# Projet_Schematics.net
KiCad netlist of a schematic drawn in EAGLE
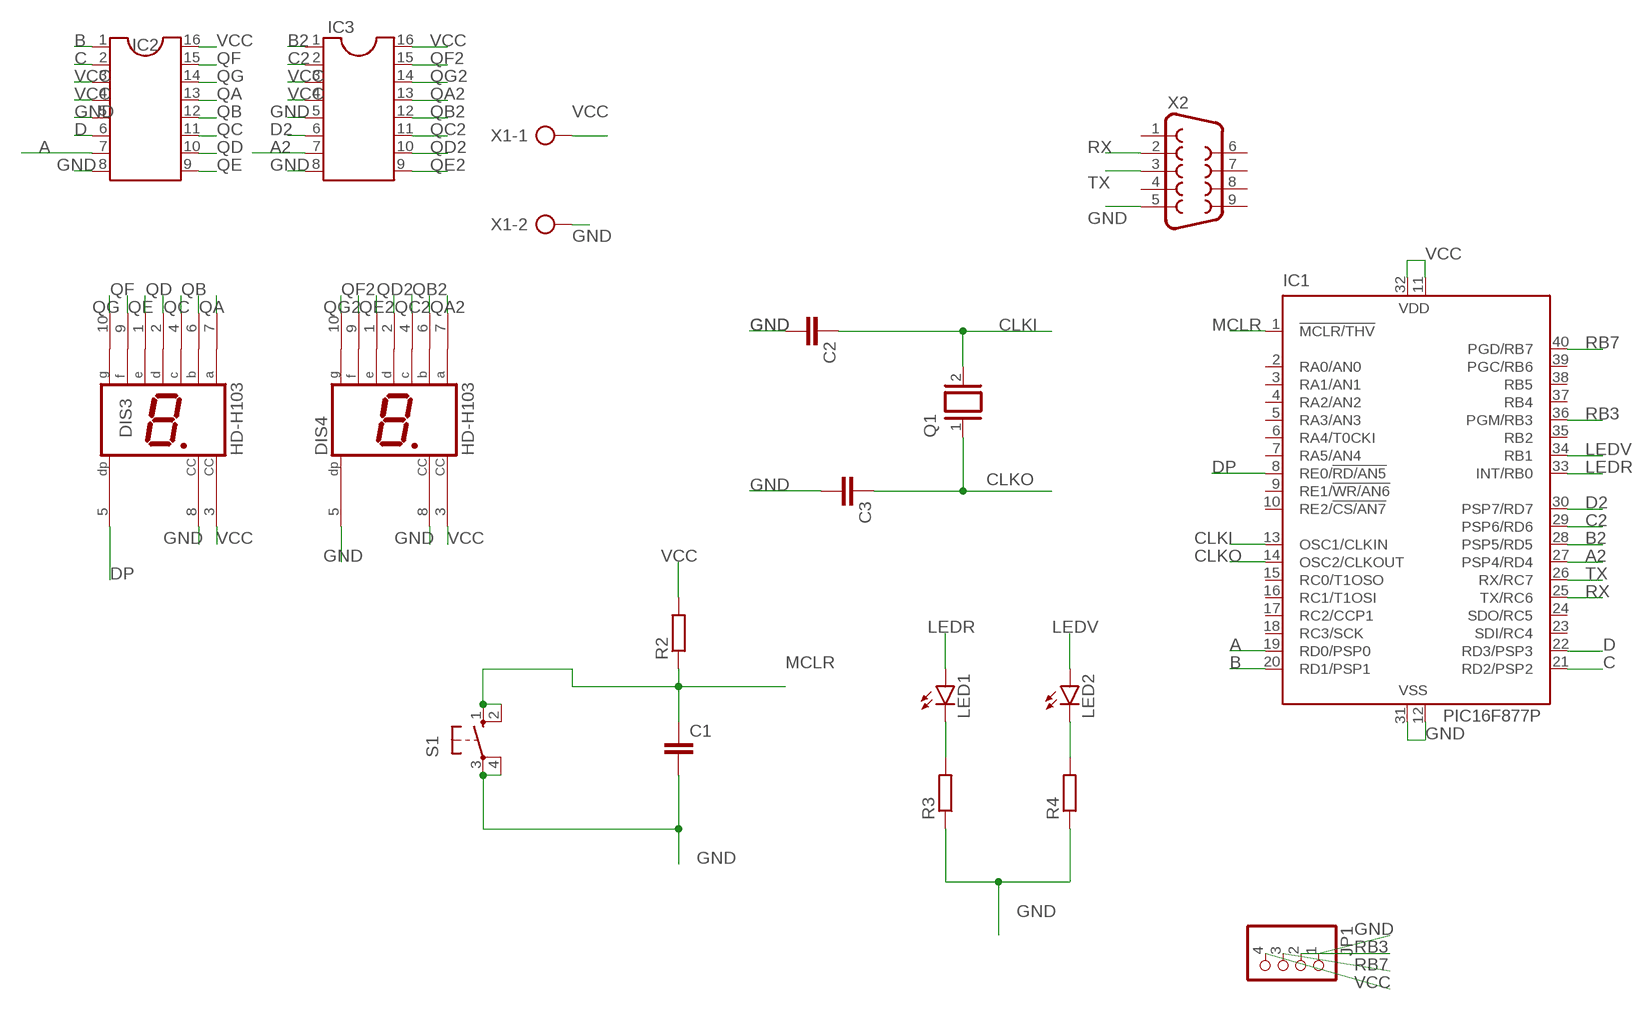
[diagram p0: schematic, sheet 1]

(export (version "E")
  (design (tool "Eeschema 10.0.6"))
  (components
    (comp (ref "C1")
      (value "C-EU025-030X050")
      (footprint "eagle-import:C025-030X050")
      (libsource (lib "eagle-import") (part "C-EU025-030X050"))
    )
    (comp (ref "C2")
      (value "C-EU025-030X050")
      (footprint "eagle-import:C025-030X050")
      (libsource (lib "eagle-import") (part "C-EU025-030X050"))
    )
    (comp (ref "C3")
      (value "C-EU025-030X050")
      (footprint "eagle-import:C025-030X050")
      (libsource (lib "eagle-import") (part "C-EU025-030X050"))
    )
    (comp (ref "DIS3")
      (value "HD-H103")
      (footprint "eagle-import:HDSP-M")
      (libsource (lib "eagle-import") (part "HD-H103"))
    )
    (comp (ref "DIS4")
      (value "HD-H103")
      (footprint "eagle-import:HDSP-M")
      (libsource (lib "eagle-import") (part "HD-H103"))
    )
    (comp (ref "IC1")
      (value "PIC16F877P")
      (footprint "eagle-import:DIL40")
      (fields (field (name "MF") "MICROCHIP") (field (name "MPN") "PIC16F877-04/P"))
      (libsource (lib "eagle-import") (part "PIC16F87P7"))
    )
    (comp (ref "IC2")
      (value "DIL16")
      (footprint "eagle-import:DIL16")
      (libsource (lib "eagle-import") (part "DIL16"))
    )
    (comp (ref "IC3")
      (value "DIL16")
      (footprint "eagle-import:DIL16")
      (libsource (lib "eagle-import") (part "DIL16"))
    )
    (comp (ref "JP1")
      (value "PINHD-1X4")
      (footprint "eagle-import:1X04")
      (libsource (lib "eagle-import") (part "PINHD-1X4"))
    )
    (comp (ref "LED1")
      (value "LED5MM")
      (footprint "eagle-import:LED5MM")
      (libsource (lib "eagle-import") (part "LED5MM"))
    )
    (comp (ref "LED2")
      (value "LED5MM")
      (footprint "eagle-import:LED5MM")
      (libsource (lib "eagle-import") (part "LED5MM"))
    )
    (comp (ref "Q1")
      (value "XTAL/S")
      (footprint "eagle-import:QS")
      (libsource (lib "eagle-import") (part "XTAL/S"))
    )
    (comp (ref "R2")
      (value "R-EU_0204/7")
      (footprint "eagle-import:0204_7")
      (libsource (lib "eagle-import") (part "R-EU_0204/7"))
    )
    (comp (ref "R3")
      (value "R-EU_0204/7")
      (footprint "eagle-import:0204_7")
      (libsource (lib "eagle-import") (part "R-EU_0204/7"))
    )
    (comp (ref "R4")
      (value "R-EU_0204/7")
      (footprint "eagle-import:0204_7")
      (libsource (lib "eagle-import") (part "R-EU_0204/7"))
    )
    (comp (ref "S1")
      (value "10-XX")
      (footprint "eagle-import:B3F-10XX")
      (fields (field (name "MPN") "B3F-1000"))
      (libsource (lib "eagle-import") (part "10-XX"))
    )
    (comp (ref "X1")
      (value "AK300/2")
      (footprint "eagle-import:AK300_2")
      (libsource (lib "eagle-import") (part "AK300/2"))
    )
    (comp (ref "X2")
      (value "F09H")
      (footprint "eagle-import:F09H")
      (libsource (lib "eagle-import") (part "F09H"))
    )
  )
  (nets
    (net (code "1") (name "/A") (class "Default")
      (node (ref "IC1") (pin "19") (pinfunction "RD0/PSP0_19") (pintype "bidirectional"))
      (node (ref "IC2") (pin "7") (pinfunction "7_7") (pintype "passive"))
    )
    (net (code "2") (name "/A2") (class "Default")
      (node (ref "IC1") (pin "27") (pinfunction "PSP4/RD4_27") (pintype "bidirectional"))
      (node (ref "IC3") (pin "7") (pinfunction "7_7") (pintype "passive"))
    )
    (net (code "3") (name "/B") (class "Default")
      (node (ref "IC1") (pin "20") (pinfunction "RD1/PSP1_20") (pintype "bidirectional"))
      (node (ref "IC2") (pin "1") (pinfunction "1_1") (pintype "passive"))
    )
    (net (code "4") (name "/B2") (class "Default")
      (node (ref "IC1") (pin "28") (pinfunction "PSP5/RD5_28") (pintype "bidirectional"))
      (node (ref "IC3") (pin "1") (pinfunction "1_1") (pintype "passive"))
    )
    (net (code "5") (name "/C") (class "Default")
      (node (ref "IC1") (pin "21") (pinfunction "RD2/PSP2_21") (pintype "bidirectional"))
      (node (ref "IC2") (pin "2") (pinfunction "2_2") (pintype "passive"))
    )
    (net (code "6") (name "/C2") (class "Default")
      (node (ref "IC1") (pin "29") (pinfunction "PSP6/RD6_29") (pintype "bidirectional"))
      (node (ref "IC3") (pin "2") (pinfunction "2_2") (pintype "passive"))
    )
    (net (code "7") (name "/CLKI") (class "Default")
      (node (ref "C2") (pin "1") (pinfunction "1_1") (pintype "passive"))
      (node (ref "IC1") (pin "13") (pinfunction "OSC1/CLKIN_13") (pintype "input"))
      (node (ref "Q1") (pin "2") (pinfunction "2_2") (pintype "passive"))
    )
    (net (code "8") (name "/CLKO") (class "Default")
      (node (ref "C3") (pin "1") (pinfunction "1_1") (pintype "passive"))
      (node (ref "IC1") (pin "14") (pinfunction "OSC2/CLKOUT_14") (pintype "output"))
      (node (ref "Q1") (pin "1") (pinfunction "1_1") (pintype "passive"))
    )
    (net (code "9") (name "/D") (class "Default")
      (node (ref "IC1") (pin "22") (pinfunction "RD3/PSP3_22") (pintype "bidirectional"))
      (node (ref "IC2") (pin "6") (pinfunction "6_6") (pintype "passive"))
    )
    (net (code "10") (name "/D2") (class "Default")
      (node (ref "IC1") (pin "30") (pinfunction "PSP7/RD7_30") (pintype "bidirectional"))
      (node (ref "IC3") (pin "6") (pinfunction "6_6") (pintype "passive"))
    )
    (net (code "11") (name "/DP") (class "Default")
      (node (ref "DIS3") (pin "5") (pinfunction "DP_5") (pintype "passive"))
      (node (ref "IC1") (pin "8") (pinfunction "RE0/~{RD/AN5}_8") (pintype "bidirectional"))
    )
    (net (code "12") (name "/GND") (class "Default")
      (node (ref "C1") (pin "2") (pinfunction "2_2") (pintype "passive"))
      (node (ref "C2") (pin "2") (pinfunction "2_2") (pintype "passive"))
      (node (ref "C3") (pin "2") (pinfunction "2_2") (pintype "passive"))
      (node (ref "DIS3") (pin "8") (pinfunction "CC_8") (pintype "passive"))
      (node (ref "DIS4") (pin "5") (pinfunction "DP_5") (pintype "passive"))
      (node (ref "DIS4") (pin "8") (pinfunction "CC_8") (pintype "passive"))
      (node (ref "IC1") (pin "12") (pinfunction "VSS_12") (pintype "power_in"))
      (node (ref "IC1") (pin "31") (pinfunction "VSS_31") (pintype "power_in"))
      (node (ref "IC2") (pin "5") (pinfunction "5_5") (pintype "passive"))
      (node (ref "IC2") (pin "8") (pinfunction "8_8") (pintype "passive"))
      (node (ref "IC3") (pin "5") (pinfunction "5_5") (pintype "passive"))
      (node (ref "IC3") (pin "8") (pinfunction "8_8") (pintype "passive"))
      (node (ref "JP1") (pin "1") (pinfunction "1_1") (pintype "passive"))
      (node (ref "R3") (pin "1") (pinfunction "1_1") (pintype "passive"))
      (node (ref "R4") (pin "1") (pinfunction "1_1") (pintype "passive"))
      (node (ref "S1") (pin "3") (pinfunction "P_3") (pintype "passive"))
      (node (ref "S1") (pin "4") (pinfunction "P1_4") (pintype "passive"))
      (node (ref "X1") (pin "2") (pinfunction "KL_2") (pintype "passive"))
      (node (ref "X2") (pin "5") (pinfunction "5_5") (pintype "passive"))
    )
    (net (code "13") (name "/LEDR") (class "Default")
      (node (ref "IC1") (pin "33") (pinfunction "INT/RB0_33") (pintype "bidirectional"))
      (node (ref "LED1") (pin "A") (pinfunction "A_A") (pintype "passive"))
    )
    (net (code "14") (name "/LEDV") (class "Default")
      (node (ref "IC1") (pin "34") (pinfunction "RB1_34") (pintype "bidirectional"))
      (node (ref "LED2") (pin "A") (pinfunction "A_A") (pintype "passive"))
    )
    (net (code "15") (name "/MCLR") (class "Default")
      (node (ref "C1") (pin "1") (pinfunction "1_1") (pintype "passive"))
      (node (ref "IC1") (pin "1") (pinfunction "~{MCLR/THV}_1") (pintype "input"))
      (node (ref "R2") (pin "1") (pinfunction "1_1") (pintype "passive"))
      (node (ref "S1") (pin "1") (pinfunction "S_1") (pintype "passive"))
      (node (ref "S1") (pin "2") (pinfunction "S1_2") (pintype "passive"))
    )
    (net (code "16") (name "/QA") (class "Default")
      (node (ref "DIS3") (pin "7") (pinfunction "A_7") (pintype "passive"))
      (node (ref "IC2") (pin "13") (pinfunction "13_13") (pintype "passive"))
    )
    (net (code "17") (name "/QA2") (class "Default")
      (node (ref "DIS4") (pin "7") (pinfunction "A_7") (pintype "passive"))
      (node (ref "IC3") (pin "13") (pinfunction "13_13") (pintype "passive"))
    )
    (net (code "18") (name "/QB") (class "Default")
      (node (ref "DIS3") (pin "6") (pinfunction "B_6") (pintype "passive"))
      (node (ref "IC2") (pin "12") (pinfunction "12_12") (pintype "passive"))
    )
    (net (code "19") (name "/QB2") (class "Default")
      (node (ref "DIS4") (pin "6") (pinfunction "B_6") (pintype "passive"))
      (node (ref "IC3") (pin "12") (pinfunction "12_12") (pintype "passive"))
    )
    (net (code "20") (name "/QC") (class "Default")
      (node (ref "DIS3") (pin "4") (pinfunction "C_4") (pintype "passive"))
      (node (ref "IC2") (pin "11") (pinfunction "11_11") (pintype "passive"))
    )
    (net (code "21") (name "/QC2") (class "Default")
      (node (ref "DIS4") (pin "4") (pinfunction "C_4") (pintype "passive"))
      (node (ref "IC3") (pin "11") (pinfunction "11_11") (pintype "passive"))
    )
    (net (code "22") (name "/QD") (class "Default")
      (node (ref "DIS3") (pin "2") (pinfunction "D_2") (pintype "passive"))
      (node (ref "IC2") (pin "10") (pinfunction "10_10") (pintype "passive"))
    )
    (net (code "23") (name "/QD2") (class "Default")
      (node (ref "DIS4") (pin "2") (pinfunction "D_2") (pintype "passive"))
      (node (ref "IC3") (pin "10") (pinfunction "10_10") (pintype "passive"))
    )
    (net (code "24") (name "/QE") (class "Default")
      (node (ref "DIS3") (pin "1") (pinfunction "E_1") (pintype "passive"))
      (node (ref "IC2") (pin "9") (pinfunction "9_9") (pintype "passive"))
    )
    (net (code "25") (name "/QE2") (class "Default")
      (node (ref "DIS4") (pin "1") (pinfunction "E_1") (pintype "passive"))
      (node (ref "IC3") (pin "9") (pinfunction "9_9") (pintype "passive"))
    )
    (net (code "26") (name "/QF") (class "Default")
      (node (ref "DIS3") (pin "9") (pinfunction "F_9") (pintype "passive"))
      (node (ref "IC2") (pin "15") (pinfunction "15_15") (pintype "passive"))
    )
    (net (code "27") (name "/QF2") (class "Default")
      (node (ref "DIS4") (pin "9") (pinfunction "F_9") (pintype "passive"))
      (node (ref "IC3") (pin "15") (pinfunction "15_15") (pintype "passive"))
    )
    (net (code "28") (name "/QG") (class "Default")
      (node (ref "DIS3") (pin "10") (pinfunction "G_10") (pintype "passive"))
      (node (ref "IC2") (pin "14") (pinfunction "14_14") (pintype "passive"))
    )
    (net (code "29") (name "/QG2") (class "Default")
      (node (ref "DIS4") (pin "10") (pinfunction "G_10") (pintype "passive"))
      (node (ref "IC3") (pin "14") (pinfunction "14_14") (pintype "passive"))
    )
    (net (code "30") (name "/RB3") (class "Default")
      (node (ref "IC1") (pin "36") (pinfunction "PGM/RB3_36") (pintype "bidirectional"))
      (node (ref "JP1") (pin "2") (pinfunction "2_2") (pintype "passive"))
    )
    (net (code "31") (name "/RB7") (class "Default")
      (node (ref "IC1") (pin "40") (pinfunction "PGD/RB7_40") (pintype "bidirectional"))
      (node (ref "JP1") (pin "3") (pinfunction "3_3") (pintype "passive"))
    )
    (net (code "32") (name "/RX") (class "Default")
      (node (ref "IC1") (pin "25") (pinfunction "TX/RC6_25") (pintype "bidirectional"))
      (node (ref "X2") (pin "2") (pinfunction "2_2") (pintype "passive"))
    )
    (net (code "33") (name "/TX") (class "Default")
      (node (ref "IC1") (pin "26") (pinfunction "RX/RC7_26") (pintype "bidirectional"))
      (node (ref "X2") (pin "3") (pinfunction "3_3") (pintype "passive"))
    )
    (net (code "34") (name "/VCC") (class "Default")
      (node (ref "DIS3") (pin "3") (pinfunction "CC_3") (pintype "passive"))
      (node (ref "DIS4") (pin "3") (pinfunction "CC_3") (pintype "passive"))
      (node (ref "IC1") (pin "11") (pinfunction "VDD_11") (pintype "power_in"))
      (node (ref "IC1") (pin "32") (pinfunction "VDD_32") (pintype "power_in"))
      (node (ref "IC2") (pin "16") (pinfunction "16_16") (pintype "passive"))
      (node (ref "IC2") (pin "3") (pinfunction "3_3") (pintype "passive"))
      (node (ref "IC2") (pin "4") (pinfunction "4_4") (pintype "passive"))
      (node (ref "IC3") (pin "16") (pinfunction "16_16") (pintype "passive"))
      (node (ref "IC3") (pin "3") (pinfunction "3_3") (pintype "passive"))
      (node (ref "IC3") (pin "4") (pinfunction "4_4") (pintype "passive"))
      (node (ref "JP1") (pin "4") (pinfunction "4_4") (pintype "passive"))
      (node (ref "R2") (pin "2") (pinfunction "2_2") (pintype "passive"))
      (node (ref "X1") (pin "1") (pinfunction "KL_1") (pintype "passive"))
    )
    (net (code "35") (name "Net-(LED1-C)") (class "Default")
      (node (ref "LED1") (pin "K") (pinfunction "C_K") (pintype "passive"))
      (node (ref "R3") (pin "2") (pinfunction "2_2") (pintype "passive"))
    )
    (net (code "36") (name "Net-(LED2-C)") (class "Default")
      (node (ref "LED2") (pin "K") (pinfunction "C_K") (pintype "passive"))
      (node (ref "R4") (pin "2") (pinfunction "2_2") (pintype "passive"))
    )
    (net (code "37") (name "unconnected-(IC1-PGC{slash}RB6-Pad39)") (class "Default")
      (node (ref "IC1") (pin "39") (pinfunction "PGC/RB6_39") (pintype "bidirectional"))
    )
    (net (code "38") (name "unconnected-(IC1-RA0{slash}AN0-Pad2)") (class "Default")
      (node (ref "IC1") (pin "2") (pinfunction "RA0/AN0_2") (pintype "bidirectional"))
    )
    (net (code "39") (name "unconnected-(IC1-RA1{slash}AN1-Pad3)") (class "Default")
      (node (ref "IC1") (pin "3") (pinfunction "RA1/AN1_3") (pintype "bidirectional"))
    )
    (net (code "40") (name "unconnected-(IC1-RA2{slash}AN2-Pad4)") (class "Default")
      (node (ref "IC1") (pin "4") (pinfunction "RA2/AN2_4") (pintype "bidirectional"))
    )
    (net (code "41") (name "unconnected-(IC1-RA3{slash}AN3-Pad5)") (class "Default")
      (node (ref "IC1") (pin "5") (pinfunction "RA3/AN3_5") (pintype "bidirectional"))
    )
    (net (code "42") (name "unconnected-(IC1-RA4{slash}T0CKI-Pad6)") (class "Default")
      (node (ref "IC1") (pin "6") (pinfunction "RA4/T0CKI_6") (pintype "bidirectional"))
    )
    (net (code "43") (name "unconnected-(IC1-RA5{slash}AN4-Pad7)") (class "Default")
      (node (ref "IC1") (pin "7") (pinfunction "RA5/AN4_7") (pintype "bidirectional"))
    )
    (net (code "44") (name "unconnected-(IC1-RB2-Pad35)") (class "Default")
      (node (ref "IC1") (pin "35") (pinfunction "RB2_35") (pintype "bidirectional"))
    )
    (net (code "45") (name "unconnected-(IC1-RB4-Pad37)") (class "Default")
      (node (ref "IC1") (pin "37") (pinfunction "RB4_37") (pintype "bidirectional"))
    )
    (net (code "46") (name "unconnected-(IC1-RB5-Pad38)") (class "Default")
      (node (ref "IC1") (pin "38") (pinfunction "RB5_38") (pintype "bidirectional"))
    )
    (net (code "47") (name "unconnected-(IC1-RC0{slash}T1OSO-Pad15)") (class "Default")
      (node (ref "IC1") (pin "15") (pinfunction "RC0/T1OSO_15") (pintype "bidirectional"))
    )
    (net (code "48") (name "unconnected-(IC1-RC1{slash}T1OSI-Pad16)") (class "Default")
      (node (ref "IC1") (pin "16") (pinfunction "RC1/T1OSI_16") (pintype "bidirectional"))
    )
    (net (code "49") (name "unconnected-(IC1-RC2{slash}CCP1-Pad17)") (class "Default")
      (node (ref "IC1") (pin "17") (pinfunction "RC2/CCP1_17") (pintype "bidirectional"))
    )
    (net (code "50") (name "unconnected-(IC1-RC3{slash}SCK-Pad18)") (class "Default")
      (node (ref "IC1") (pin "18") (pinfunction "RC3/SCK_18") (pintype "bidirectional"))
    )
    (net (code "51") (name "unconnected-(IC1-RE1{slash}~{WR{slash}AN6}-Pad9)") (class "Default")
      (node (ref "IC1") (pin "9") (pinfunction "RE1/~{WR/AN6}_9") (pintype "bidirectional"))
    )
    (net (code "52") (name "unconnected-(IC1-RE2{slash}~{CS{slash}AN7}-Pad10)") (class "Default")
      (node (ref "IC1") (pin "10") (pinfunction "RE2/~{CS/AN7}_10") (pintype "bidirectional"))
    )
    (net (code "53") (name "unconnected-(IC1-SDI{slash}RC4-Pad23)") (class "Default")
      (node (ref "IC1") (pin "23") (pinfunction "SDI/RC4_23") (pintype "bidirectional"))
    )
    (net (code "54") (name "unconnected-(IC1-SDO{slash}RC5-Pad24)") (class "Default")
      (node (ref "IC1") (pin "24") (pinfunction "SDO/RC5_24") (pintype "bidirectional"))
    )
    (net (code "55") (name "unconnected-(X2-Pad1)") (class "Default")
      (node (ref "X2") (pin "1") (pinfunction "1_1") (pintype "passive"))
    )
    (net (code "56") (name "unconnected-(X2-Pad4)") (class "Default")
      (node (ref "X2") (pin "4") (pinfunction "4_4") (pintype "passive"))
    )
    (net (code "57") (name "unconnected-(X2-Pad6)") (class "Default")
      (node (ref "X2") (pin "6") (pinfunction "6_6") (pintype "passive"))
    )
    (net (code "58") (name "unconnected-(X2-Pad7)") (class "Default")
      (node (ref "X2") (pin "7") (pinfunction "7_7") (pintype "passive"))
    )
    (net (code "59") (name "unconnected-(X2-Pad8)") (class "Default")
      (node (ref "X2") (pin "8") (pinfunction "8_8") (pintype "passive"))
    )
    (net (code "60") (name "unconnected-(X2-Pad9)") (class "Default")
      (node (ref "X2") (pin "9") (pinfunction "9_9") (pintype "passive"))
    )
  )
)
